# asserv_v2.net
KiCad netlist of a schematic drawn in EAGLE
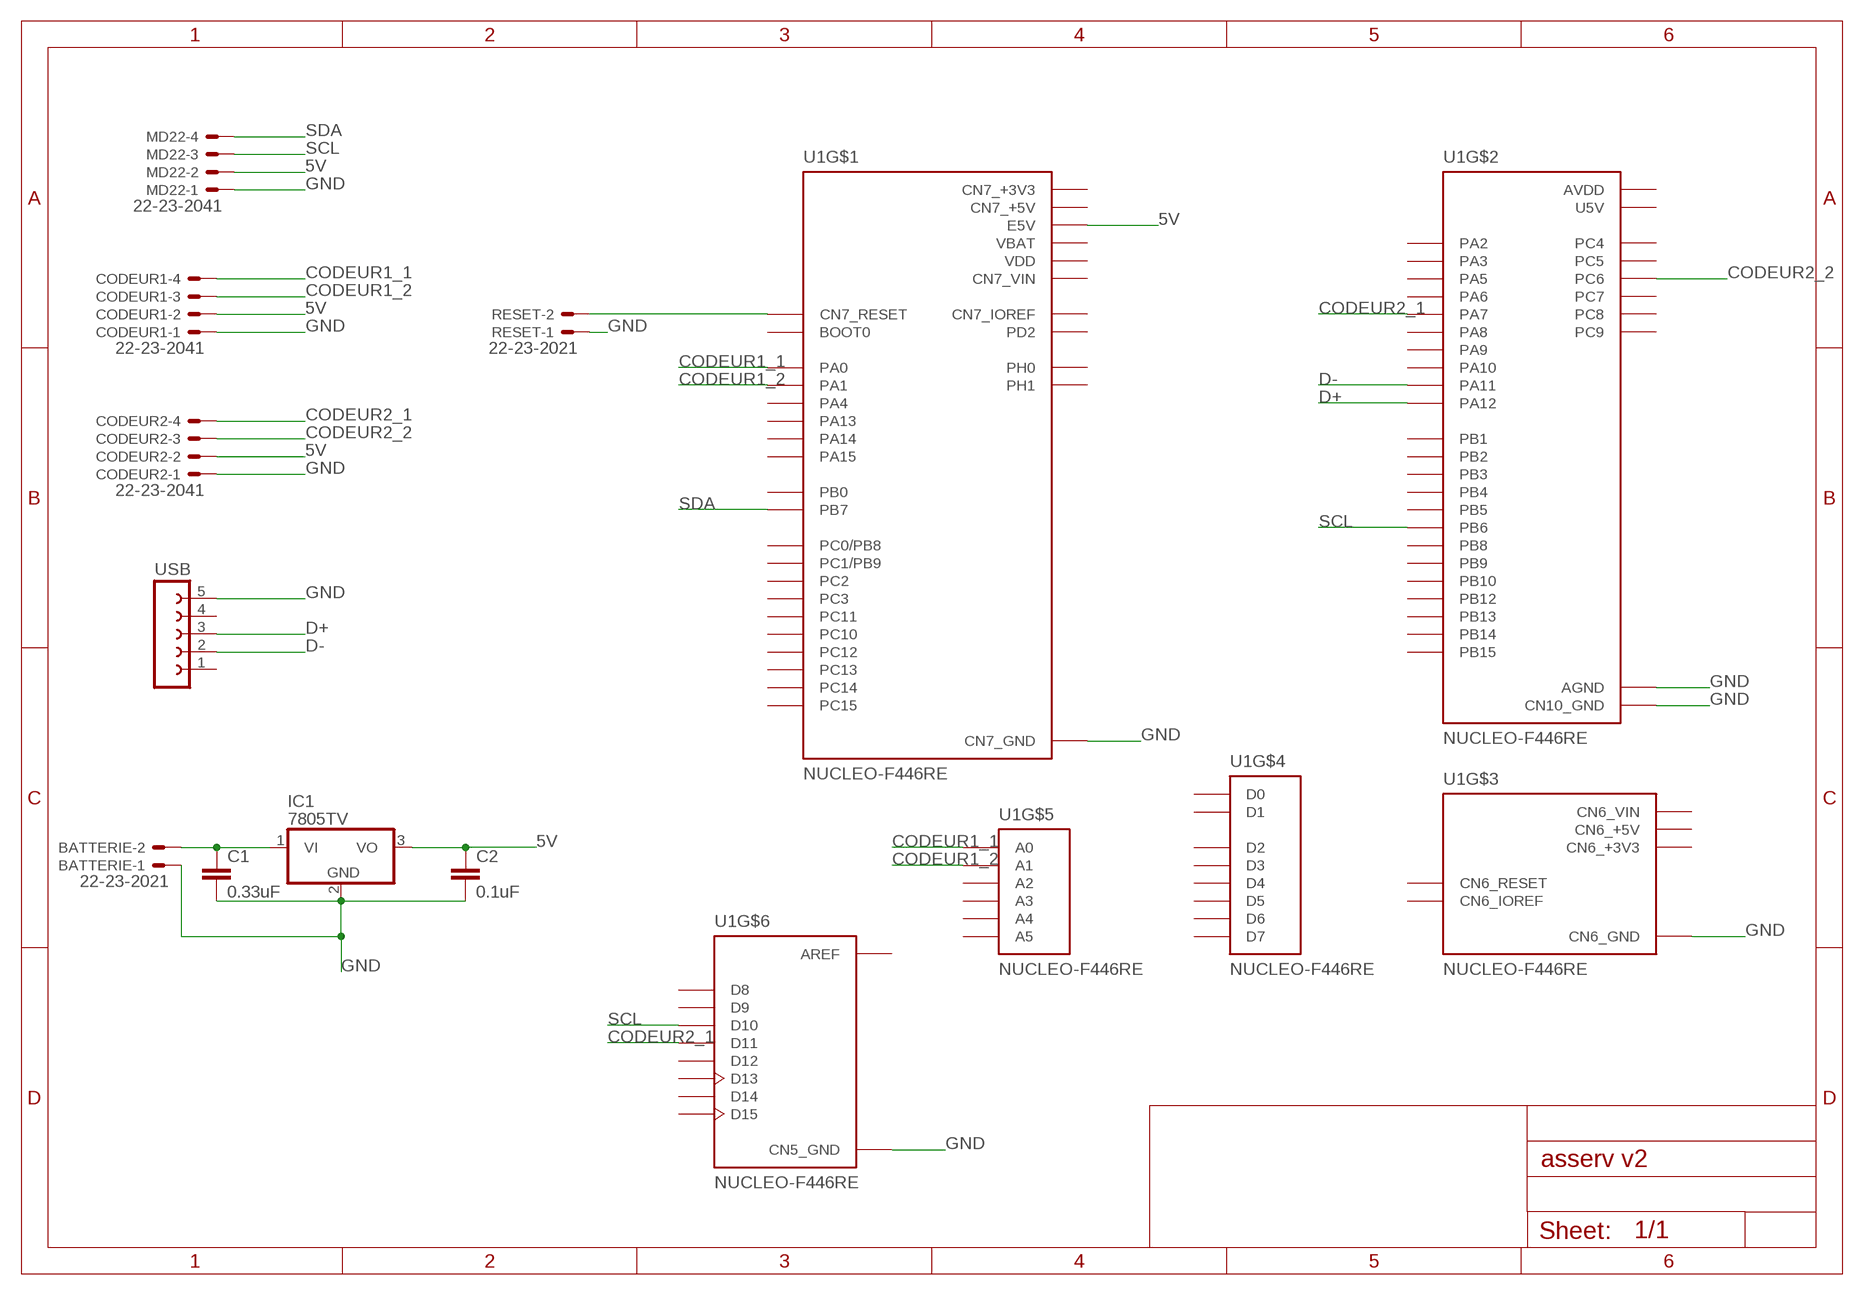
[diagram p0: schematic, sheet 1]

(export (version "E")
  (design (tool "Eeschema 10.0.6"))
  (components
    (comp (ref "BATTERIE")
      (value "22-23-2021")
      (footprint "eagle-import:22-23-2021")
      (fields (field (name "MF") "MOLEX"))
      (libsource (lib "eagle-import") (part "22-23-2021"))
    )
    (comp (ref "C1")
      (value "0.33uF")
      (footprint "eagle-import:C5B2.5")
      (libsource (lib "eagle-import") (part "C5/2.5"))
    )
    (comp (ref "C2")
      (value "0.1uF")
      (footprint "eagle-import:C5B2.5")
      (libsource (lib "eagle-import") (part "C5/2.5"))
    )
    (comp (ref "CODEUR1")
      (value "22-23-2041")
      (footprint "eagle-import:22-23-2041")
      (fields (field (name "MF") "MOLEX"))
      (libsource (lib "eagle-import") (part "22-23-2041"))
    )
    (comp (ref "CODEUR2")
      (value "22-23-2041")
      (footprint "eagle-import:22-23-2041")
      (fields (field (name "MF") "MOLEX"))
      (libsource (lib "eagle-import") (part "22-23-2041"))
    )
    (comp (ref "IC1")
      (value "7805TV")
      (footprint "eagle-import:TO220V")
      (libsource (lib "eagle-import") (part "78TV05"))
    )
    (comp (ref "MD22")
      (value "22-23-2041")
      (footprint "eagle-import:22-23-2041")
      (fields (field (name "MF") "MOLEX"))
      (libsource (lib "eagle-import") (part "22-23-2041"))
    )
    (comp (ref "RESET")
      (value "22-23-2021")
      (footprint "eagle-import:22-23-2021")
      (fields (field (name "MF") "MOLEX"))
      (libsource (lib "eagle-import") (part "22-23-2021"))
    )
    (comp (ref "U1")
      (value "NUCLEO-F446RE")
      (footprint "eagle-import:MODULE_NUCLEO-F446RE")
      (fields
        (field (name "MF") "STMicroelectronics")
        (field (name "MF_1") "STMICROELECTRONICS")
        (field (name "MPN") "NUCLEO-F446RE")
        (field (name "OC_FARNELL") "2491978")
        (field (name "SPICEPREFIX") "X")
      )
      (libsource (lib "eagle-import") (part "NUCLEO-F446RE"))
    )
    (comp (ref "USB")
      (value "FE05-1")
      (footprint "eagle-import:FE05-1")
      (libsource (lib "eagle-import") (part "FE05-1"))
    )
  )
  (nets
    (net (code "1") (name "/5V") (class "Default")
      (node (ref "C2") (pin "1") (pinfunction "1_1") (pintype "passive"))
      (node (ref "CODEUR1") (pin "2") (pinfunction "S_2") (pintype "passive"))
      (node (ref "CODEUR2") (pin "2") (pinfunction "S_2") (pintype "passive"))
      (node (ref "IC1") (pin "3") (pinfunction "VO_3") (pintype "passive"))
      (node (ref "MD22") (pin "2") (pinfunction "S_2") (pintype "passive"))
      (node (ref "U1") (pin "CN7_6") (pinfunction "E5V_CN7_6") (pintype "power_in"))
    )
    (net (code "2") (name "/AREF") (class "Default")
      (node (ref "U1") (pin "CN5_8") (pinfunction "AREF_CN5_8") (pintype "power_in"))
    )
    (net (code "3") (name "/AVDD") (class "Default")
      (node (ref "U1") (pin "CN10_7") (pinfunction "AVDD_CN10_7") (pintype "power_in"))
    )
    (net (code "4") (name "/CN6_+3V3") (class "Default")
      (node (ref "U1") (pin "CN6_4") (pinfunction "CN6_+3V3_CN6_4") (pintype "power_in"))
    )
    (net (code "5") (name "/CN6_+5V") (class "Default")
      (node (ref "U1") (pin "CN6_5") (pinfunction "CN6_+5V_CN6_5") (pintype "power_in"))
    )
    (net (code "6") (name "/CN6_VIN") (class "Default")
      (node (ref "U1") (pin "CN6_8") (pinfunction "CN6_VIN_CN6_8") (pintype "power_in"))
    )
    (net (code "7") (name "/CN7_+3V3") (class "Default")
      (node (ref "U1") (pin "CN7_16") (pinfunction "CN7_+3V3_CN7_16") (pintype "power_in"))
    )
    (net (code "8") (name "/CN7_+5V") (class "Default")
      (node (ref "U1") (pin "CN7_18") (pinfunction "CN7_+5V_CN7_18") (pintype "power_in"))
    )
    (net (code "9") (name "/CN7_VIN") (class "Default")
      (node (ref "U1") (pin "CN7_24") (pinfunction "CN7_VIN_CN7_24") (pintype "power_in"))
    )
    (net (code "10") (name "/CODEUR1_1") (class "Default")
      (node (ref "CODEUR1") (pin "4") (pinfunction "S_4") (pintype "passive"))
      (node (ref "U1") (pin "CN7_28") (pinfunction "PA0_CN7_28") (pintype "bidirectional"))
      (node (ref "U1") (pin "CN8_1") (pinfunction "A0_CN8_1") (pintype "input"))
    )
    (net (code "11") (name "/CODEUR1_2") (class "Default")
      (node (ref "CODEUR1") (pin "3") (pinfunction "S_3") (pintype "passive"))
      (node (ref "U1") (pin "CN7_30") (pinfunction "PA1_CN7_30") (pintype "bidirectional"))
      (node (ref "U1") (pin "CN8_2") (pinfunction "A1_CN8_2") (pintype "input"))
    )
    (net (code "12") (name "/CODEUR2_1") (class "Default")
      (node (ref "CODEUR2") (pin "4") (pinfunction "S_4") (pintype "passive"))
      (node (ref "U1") (pin "CN10_15") (pinfunction "PA7_CN10_15") (pintype "bidirectional"))
      (node (ref "U1") (pin "CN5_4") (pinfunction "D11_CN5_4") (pintype "bidirectional"))
    )
    (net (code "13") (name "/CODEUR2_2") (class "Default")
      (node (ref "CODEUR2") (pin "3") (pinfunction "S_3") (pintype "passive"))
      (node (ref "U1") (pin "CN10_4") (pinfunction "PC6_CN10_4") (pintype "bidirectional"))
    )
    (net (code "14") (name "/D+") (class "Default")
      (node (ref "U1") (pin "CN10_12") (pinfunction "PA12_CN10_12") (pintype "bidirectional"))
      (node (ref "USB") (pin "3") (pinfunction "3_3") (pintype "passive"))
    )
    (net (code "15") (name "/D-") (class "Default")
      (node (ref "U1") (pin "CN10_14") (pinfunction "PA11_CN10_14") (pintype "bidirectional"))
      (node (ref "USB") (pin "2") (pinfunction "2_2") (pintype "passive"))
    )
    (net (code "16") (name "/GND") (class "Default")
      (node (ref "BATTERIE") (pin "1") (pinfunction "S_1") (pintype "passive"))
      (node (ref "C1") (pin "2") (pinfunction "2_2") (pintype "passive"))
      (node (ref "C2") (pin "2") (pinfunction "2_2") (pintype "passive"))
      (node (ref "CODEUR1") (pin "1") (pinfunction "S_1") (pintype "passive"))
      (node (ref "CODEUR2") (pin "1") (pinfunction "S_1") (pintype "passive"))
      (node (ref "IC1") (pin "2") (pinfunction "GND_2") (pintype "passive"))
      (node (ref "MD22") (pin "1") (pinfunction "S_1") (pintype "passive"))
      (node (ref "RESET") (pin "1") (pinfunction "S_1") (pintype "passive"))
      (node (ref "U1") (pin "CN10_20") (pinfunction "CN10_GND_CN10_20") (pintype "power_in"))
      (node (ref "U1") (pin "CN10_32") (pinfunction "AGND_CN10_32") (pintype "power_in"))
      (node (ref "U1") (pin "CN10_9") (pinfunction "CN10_GND_CN10_9") (pintype "power_in"))
      (node (ref "U1") (pin "CN5_7") (pinfunction "CN5_GND_CN5_7") (pintype "power_in"))
      (node (ref "U1") (pin "CN6_6") (pinfunction "CN6_GND_CN6_6") (pintype "power_in"))
      (node (ref "U1") (pin "CN6_7") (pinfunction "CN6_GND_CN6_7") (pintype "power_in"))
      (node (ref "U1") (pin "CN7_19") (pinfunction "CN7_GND_CN7_19") (pintype "power_in"))
      (node (ref "U1") (pin "CN7_20") (pinfunction "CN7_GND_CN7_20") (pintype "power_in"))
      (node (ref "U1") (pin "CN7_22") (pinfunction "CN7_GND_CN7_22") (pintype "power_in"))
      (node (ref "U1") (pin "CN7_8") (pinfunction "CN7_GND_CN7_8") (pintype "power_in"))
      (node (ref "USB") (pin "5") (pinfunction "5_5") (pintype "passive"))
    )
    (net (code "17") (name "/SCL") (class "Default")
      (node (ref "MD22") (pin "3") (pinfunction "S_3") (pintype "passive"))
      (node (ref "U1") (pin "CN10_17") (pinfunction "PB6_CN10_17") (pintype "bidirectional"))
      (node (ref "U1") (pin "CN5_3") (pinfunction "D10_CN5_3") (pintype "bidirectional"))
    )
    (net (code "18") (name "/SDA") (class "Default")
      (node (ref "MD22") (pin "4") (pinfunction "S_4") (pintype "passive"))
      (node (ref "U1") (pin "CN7_21") (pinfunction "PB7_CN7_21") (pintype "bidirectional"))
    )
    (net (code "19") (name "/U5V") (class "Default")
      (node (ref "U1") (pin "CN10_8") (pinfunction "U5V_CN10_8") (pintype "power_in"))
    )
    (net (code "20") (name "/VBAT") (class "Default")
      (node (ref "U1") (pin "CN7_33") (pinfunction "VBAT_CN7_33") (pintype "power_in"))
    )
    (net (code "21") (name "/VDD") (class "Default")
      (node (ref "U1") (pin "CN7_5") (pinfunction "VDD_CN7_5") (pintype "power_in"))
    )
    (net (code "22") (name "Net-(BATTERIEB-S)") (class "Default")
      (node (ref "BATTERIE") (pin "2") (pinfunction "S_2") (pintype "passive"))
      (node (ref "C1") (pin "1") (pinfunction "1_1") (pintype "passive"))
      (node (ref "IC1") (pin "1") (pinfunction "VI_1") (pintype "input"))
    )
    (net (code "23") (name "Net-(RESETB-S)") (class "Default")
      (node (ref "RESET") (pin "2") (pinfunction "S_2") (pintype "passive"))
      (node (ref "U1") (pin "CN7_14") (pinfunction "CN7_RESET_CN7_14") (pintype "bidirectional"))
    )
    (net (code "24") (name "unconnected-(U1A-BOOT0-PadCN7_7)") (class "Default")
      (node (ref "U1") (pin "CN7_7") (pinfunction "BOOT0_CN7_7") (pintype "bidirectional"))
    )
    (net (code "25") (name "unconnected-(U1A-CN7_IOREF-PadCN7_12)") (class "Default")
      (node (ref "U1") (pin "CN7_12") (pinfunction "CN7_IOREF_CN7_12") (pintype "bidirectional"))
    )
    (net (code "26") (name "unconnected-(U1A-PA4-PadCN7_32)") (class "Default")
      (node (ref "U1") (pin "CN7_32") (pinfunction "PA4_CN7_32") (pintype "bidirectional"))
    )
    (net (code "27") (name "unconnected-(U1A-PA13-PadCN7_13)") (class "Default")
      (node (ref "U1") (pin "CN7_13") (pinfunction "PA13_CN7_13") (pintype "bidirectional"))
    )
    (net (code "28") (name "unconnected-(U1A-PA14-PadCN7_15)") (class "Default")
      (node (ref "U1") (pin "CN7_15") (pinfunction "PA14_CN7_15") (pintype "bidirectional"))
    )
    (net (code "29") (name "unconnected-(U1A-PA15-PadCN7_17)") (class "Default")
      (node (ref "U1") (pin "CN7_17") (pinfunction "PA15_CN7_17") (pintype "bidirectional"))
    )
    (net (code "30") (name "unconnected-(U1A-PB0-PadCN7_34)") (class "Default")
      (node (ref "U1") (pin "CN7_34") (pinfunction "PB0_CN7_34") (pintype "bidirectional"))
    )
    (net (code "31") (name "unconnected-(U1A-PC0{slash}PB8-PadCN7_38)") (class "Default")
      (node (ref "U1") (pin "CN7_38") (pinfunction "PC0/PB8_CN7_38") (pintype "bidirectional"))
    )
    (net (code "32") (name "unconnected-(U1A-PC1{slash}PB9-PadCN7_36)") (class "Default")
      (node (ref "U1") (pin "CN7_36") (pinfunction "PC1/PB9_CN7_36") (pintype "bidirectional"))
    )
    (net (code "33") (name "unconnected-(U1A-PC2-PadCN7_35)") (class "Default")
      (node (ref "U1") (pin "CN7_35") (pinfunction "PC2_CN7_35") (pintype "bidirectional"))
    )
    (net (code "34") (name "unconnected-(U1A-PC3-PadCN7_37)") (class "Default")
      (node (ref "U1") (pin "CN7_37") (pinfunction "PC3_CN7_37") (pintype "bidirectional"))
    )
    (net (code "35") (name "unconnected-(U1A-PC10-PadCN7_1)") (class "Default")
      (node (ref "U1") (pin "CN7_1") (pinfunction "PC10_CN7_1") (pintype "bidirectional"))
    )
    (net (code "36") (name "unconnected-(U1A-PC11-PadCN7_2)") (class "Default")
      (node (ref "U1") (pin "CN7_2") (pinfunction "PC11_CN7_2") (pintype "bidirectional"))
    )
    (net (code "37") (name "unconnected-(U1A-PC12-PadCN7_3)") (class "Default")
      (node (ref "U1") (pin "CN7_3") (pinfunction "PC12_CN7_3") (pintype "bidirectional"))
    )
    (net (code "38") (name "unconnected-(U1A-PC13-PadCN7_23)") (class "Default")
      (node (ref "U1") (pin "CN7_23") (pinfunction "PC13_CN7_23") (pintype "bidirectional"))
    )
    (net (code "39") (name "unconnected-(U1A-PC14-PadCN7_25)") (class "Default")
      (node (ref "U1") (pin "CN7_25") (pinfunction "PC14_CN7_25") (pintype "bidirectional"))
    )
    (net (code "40") (name "unconnected-(U1A-PC15-PadCN7_27)") (class "Default")
      (node (ref "U1") (pin "CN7_27") (pinfunction "PC15_CN7_27") (pintype "bidirectional"))
    )
    (net (code "41") (name "unconnected-(U1A-PD2-PadCN7_4)") (class "Default")
      (node (ref "U1") (pin "CN7_4") (pinfunction "PD2_CN7_4") (pintype "bidirectional"))
    )
    (net (code "42") (name "unconnected-(U1A-PH0-PadCN7_29)") (class "Default")
      (node (ref "U1") (pin "CN7_29") (pinfunction "PH0_CN7_29") (pintype "bidirectional"))
    )
    (net (code "43") (name "unconnected-(U1A-PH1-PadCN7_31)") (class "Default")
      (node (ref "U1") (pin "CN7_31") (pinfunction "PH1_CN7_31") (pintype "bidirectional"))
    )
    (net (code "44") (name "unconnected-(U1B-PA2-PadCN10_35)") (class "Default")
      (node (ref "U1") (pin "CN10_35") (pinfunction "PA2_CN10_35") (pintype "bidirectional"))
    )
    (net (code "45") (name "unconnected-(U1B-PA3-PadCN10_37)") (class "Default")
      (node (ref "U1") (pin "CN10_37") (pinfunction "PA3_CN10_37") (pintype "bidirectional"))
    )
    (net (code "46") (name "unconnected-(U1B-PA5-PadCN10_11)") (class "Default")
      (node (ref "U1") (pin "CN10_11") (pinfunction "PA5_CN10_11") (pintype "bidirectional"))
    )
    (net (code "47") (name "unconnected-(U1B-PA6-PadCN10_13)") (class "Default")
      (node (ref "U1") (pin "CN10_13") (pinfunction "PA6_CN10_13") (pintype "bidirectional"))
    )
    (net (code "48") (name "unconnected-(U1B-PA8-PadCN10_23)") (class "Default")
      (node (ref "U1") (pin "CN10_23") (pinfunction "PA8_CN10_23") (pintype "bidirectional"))
    )
    (net (code "49") (name "unconnected-(U1B-PA9-PadCN10_21)") (class "Default")
      (node (ref "U1") (pin "CN10_21") (pinfunction "PA9_CN10_21") (pintype "bidirectional"))
    )
    (net (code "50") (name "unconnected-(U1B-PA10-PadCN10_33)") (class "Default")
      (node (ref "U1") (pin "CN10_33") (pinfunction "PA10_CN10_33") (pintype "bidirectional"))
    )
    (net (code "51") (name "unconnected-(U1B-PB1-PadCN10_24)") (class "Default")
      (node (ref "U1") (pin "CN10_24") (pinfunction "PB1_CN10_24") (pintype "bidirectional"))
    )
    (net (code "52") (name "unconnected-(U1B-PB2-PadCN10_22)") (class "Default")
      (node (ref "U1") (pin "CN10_22") (pinfunction "PB2_CN10_22") (pintype "bidirectional"))
    )
    (net (code "53") (name "unconnected-(U1B-PB3-PadCN10_31)") (class "Default")
      (node (ref "U1") (pin "CN10_31") (pinfunction "PB3_CN10_31") (pintype "bidirectional"))
    )
    (net (code "54") (name "unconnected-(U1B-PB4-PadCN10_27)") (class "Default")
      (node (ref "U1") (pin "CN10_27") (pinfunction "PB4_CN10_27") (pintype "bidirectional"))
    )
    (net (code "55") (name "unconnected-(U1B-PB5-PadCN10_29)") (class "Default")
      (node (ref "U1") (pin "CN10_29") (pinfunction "PB5_CN10_29") (pintype "bidirectional"))
    )
    (net (code "56") (name "unconnected-(U1B-PB8-PadCN10_3)") (class "Default")
      (node (ref "U1") (pin "CN10_3") (pinfunction "PB8_CN10_3") (pintype "bidirectional"))
    )
    (net (code "57") (name "unconnected-(U1B-PB9-PadCN10_5)") (class "Default")
      (node (ref "U1") (pin "CN10_5") (pinfunction "PB9_CN10_5") (pintype "bidirectional"))
    )
    (net (code "58") (name "unconnected-(U1B-PB10-PadCN10_25)") (class "Default")
      (node (ref "U1") (pin "CN10_25") (pinfunction "PB10_CN10_25") (pintype "bidirectional"))
    )
    (net (code "59") (name "unconnected-(U1B-PB12-PadCN10_16)") (class "Default")
      (node (ref "U1") (pin "CN10_16") (pinfunction "PB12_CN10_16") (pintype "bidirectional"))
    )
    (net (code "60") (name "unconnected-(U1B-PB13-PadCN10_30)") (class "Default")
      (node (ref "U1") (pin "CN10_30") (pinfunction "PB13_CN10_30") (pintype "bidirectional"))
    )
    (net (code "61") (name "unconnected-(U1B-PB14-PadCN10_28)") (class "Default")
      (node (ref "U1") (pin "CN10_28") (pinfunction "PB14_CN10_28") (pintype "bidirectional"))
    )
    (net (code "62") (name "unconnected-(U1B-PB15-PadCN10_26)") (class "Default")
      (node (ref "U1") (pin "CN10_26") (pinfunction "PB15_CN10_26") (pintype "bidirectional"))
    )
    (net (code "63") (name "unconnected-(U1B-PC4-PadCN10_34)") (class "Default")
      (node (ref "U1") (pin "CN10_34") (pinfunction "PC4_CN10_34") (pintype "bidirectional"))
    )
    (net (code "64") (name "unconnected-(U1B-PC5-PadCN10_6)") (class "Default")
      (node (ref "U1") (pin "CN10_6") (pinfunction "PC5_CN10_6") (pintype "bidirectional"))
    )
    (net (code "65") (name "unconnected-(U1B-PC7-PadCN10_19)") (class "Default")
      (node (ref "U1") (pin "CN10_19") (pinfunction "PC7_CN10_19") (pintype "bidirectional"))
    )
    (net (code "66") (name "unconnected-(U1B-PC8-PadCN10_2)") (class "Default")
      (node (ref "U1") (pin "CN10_2") (pinfunction "PC8_CN10_2") (pintype "bidirectional"))
    )
    (net (code "67") (name "unconnected-(U1B-PC9-PadCN10_1)") (class "Default")
      (node (ref "U1") (pin "CN10_1") (pinfunction "PC9_CN10_1") (pintype "bidirectional"))
    )
    (net (code "68") (name "unconnected-(U1C-CN6_IOREF-PadCN6_2)") (class "Default")
      (node (ref "U1") (pin "CN6_2") (pinfunction "CN6_IOREF_CN6_2") (pintype "bidirectional"))
    )
    (net (code "69") (name "unconnected-(U1C-CN6_RESET-PadCN6_3)") (class "Default")
      (node (ref "U1") (pin "CN6_3") (pinfunction "CN6_RESET_CN6_3") (pintype "bidirectional"))
    )
    (net (code "70") (name "unconnected-(U1D-D0-PadCN9_1)") (class "Default")
      (node (ref "U1") (pin "CN9_1") (pinfunction "D0_CN9_1") (pintype "input"))
    )
    (net (code "71") (name "unconnected-(U1D-D1-PadCN9_2)") (class "Default")
      (node (ref "U1") (pin "CN9_2") (pinfunction "D1_CN9_2") (pintype "output"))
    )
    (net (code "72") (name "unconnected-(U1D-D2-PadCN9_3)") (class "Default")
      (node (ref "U1") (pin "CN9_3") (pinfunction "D2_CN9_3") (pintype "bidirectional"))
    )
    (net (code "73") (name "unconnected-(U1D-D3-PadCN9_4)") (class "Default")
      (node (ref "U1") (pin "CN9_4") (pinfunction "D3_CN9_4") (pintype "bidirectional"))
    )
    (net (code "74") (name "unconnected-(U1D-D4-PadCN9_5)") (class "Default")
      (node (ref "U1") (pin "CN9_5") (pinfunction "D4_CN9_5") (pintype "bidirectional"))
    )
    (net (code "75") (name "unconnected-(U1D-D5-PadCN9_6)") (class "Default")
      (node (ref "U1") (pin "CN9_6") (pinfunction "D5_CN9_6") (pintype "bidirectional"))
    )
    (net (code "76") (name "unconnected-(U1D-D6-PadCN9_7)") (class "Default")
      (node (ref "U1") (pin "CN9_7") (pinfunction "D6_CN9_7") (pintype "bidirectional"))
    )
    (net (code "77") (name "unconnected-(U1D-D7-PadCN9_8)") (class "Default")
      (node (ref "U1") (pin "CN9_8") (pinfunction "D7_CN9_8") (pintype "bidirectional"))
    )
    (net (code "78") (name "unconnected-(U1E-A2-PadCN8_3)") (class "Default")
      (node (ref "U1") (pin "CN8_3") (pinfunction "A2_CN8_3") (pintype "input"))
    )
    (net (code "79") (name "unconnected-(U1E-A3-PadCN8_4)") (class "Default")
      (node (ref "U1") (pin "CN8_4") (pinfunction "A3_CN8_4") (pintype "input"))
    )
    (net (code "80") (name "unconnected-(U1E-A4-PadCN8_5)") (class "Default")
      (node (ref "U1") (pin "CN8_5") (pinfunction "A4_CN8_5") (pintype "input"))
    )
    (net (code "81") (name "unconnected-(U1E-A5-PadCN8_6)") (class "Default")
      (node (ref "U1") (pin "CN8_6") (pinfunction "A5_CN8_6") (pintype "input"))
    )
    (net (code "82") (name "unconnected-(U1F-D8-PadCN5_1)") (class "Default")
      (node (ref "U1") (pin "CN5_1") (pinfunction "D8_CN5_1") (pintype "bidirectional"))
    )
    (net (code "83") (name "unconnected-(U1F-D9-PadCN5_2)") (class "Default")
      (node (ref "U1") (pin "CN5_2") (pinfunction "D9_CN5_2") (pintype "bidirectional"))
    )
    (net (code "84") (name "unconnected-(U1F-D12-PadCN5_5)") (class "Default")
      (node (ref "U1") (pin "CN5_5") (pinfunction "D12_CN5_5") (pintype "bidirectional"))
    )
    (net (code "85") (name "unconnected-(U1F-D13-PadCN5_6)") (class "Default")
      (node (ref "U1") (pin "CN5_6") (pinfunction "D13_CN5_6") (pintype "bidirectional"))
    )
    (net (code "86") (name "unconnected-(U1F-D14-PadCN5_9)") (class "Default")
      (node (ref "U1") (pin "CN5_9") (pinfunction "D14_CN5_9") (pintype "bidirectional"))
    )
    (net (code "87") (name "unconnected-(U1F-D15-PadCN5_10)") (class "Default")
      (node (ref "U1") (pin "CN5_10") (pinfunction "D15_CN5_10") (pintype "bidirectional"))
    )
    (net (code "88") (name "unconnected-(USB-Pad1)") (class "Default")
      (node (ref "USB") (pin "1") (pinfunction "1_1") (pintype "passive"))
    )
    (net (code "89") (name "unconnected-(USB-Pad4)") (class "Default")
      (node (ref "USB") (pin "4") (pinfunction "4_4") (pintype "passive"))
    )
  )
)
